# Peripheral_Circuit_A.net
KiCad netlist of a schematic drawn in Altium Designer
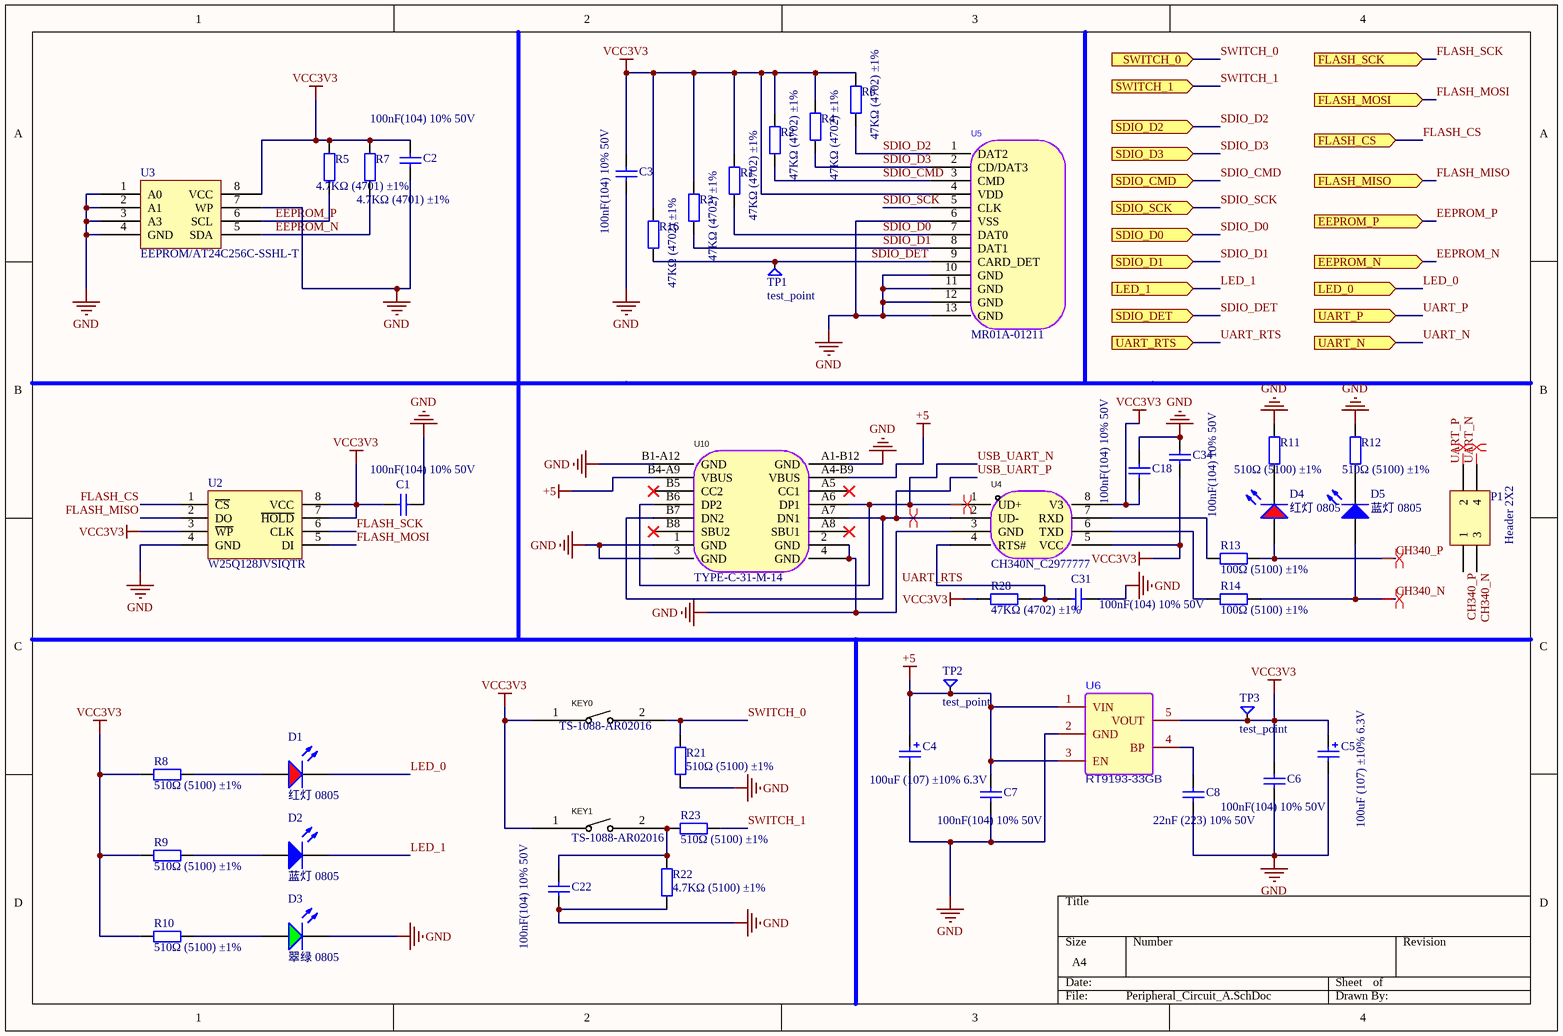
[diagram p0: Peripheral_Circuit_A.SchDoc]

(export (version "E")
  (design (tool "Eeschema 10.0.6"))
  (components
    (comp (ref "C1")
      (value "100nF(104) 10% 50V")
      (footprint "0805_C")
      (description "贴片电容")
      (libsource (lib "Miscellaneous Devices LC") (part "0805 100nF(104) 10% 50V"))
    )
    (comp (ref "C2")
      (value "100nF(104) 10% 50V")
      (footprint "0805_C")
      (description "贴片电容")
      (libsource (lib "Miscellaneous Devices LC") (part "0805 100nF(104) 10% 50V"))
    )
    (comp (ref "C3")
      (value "100nF(104) 10% 50V")
      (footprint "0805_C")
      (description "贴片电容")
      (libsource (lib "Miscellaneous Devices LC") (part "0805 100nF(104) 10% 50V"))
    )
    (comp (ref "C4")
      (value "100uF (107) ±10% 6.3V")
      (footprint "CAP-SMD_BD5.0-L5.3-W5.3-LS6.1-FD-1")
      (description "钽电容")
      (libsource (lib "Miscellaneous Devices LC") (part "3528 100uF (107) 10% 6.3V"))
    )
    (comp (ref "C5")
      (value "100uF (107) ±10% 6.3V")
      (footprint "CAP-SMD_BD5.0-L5.3-W5.3-LS6.1-FD-1")
      (description "钽电容")
      (libsource (lib "Miscellaneous Devices LC") (part "3528 100uF (107) 10% 6.3V"))
    )
    (comp (ref "C6")
      (value "100nF(104) 10% 50V")
      (footprint "0805_C")
      (description "贴片电容")
      (libsource (lib "Miscellaneous Devices LC") (part "0805 100nF(104) 10% 50V"))
    )
    (comp (ref "C7")
      (value "100nF(104) 10% 50V")
      (footprint "0805_C")
      (description "贴片电容")
      (libsource (lib "Miscellaneous Devices LC") (part "0805 100nF(104) 10% 50V"))
    )
    (comp (ref "C8")
      (value "22nF (223) 10% 50V")
      (footprint "0805_C")
      (description "贴片电容")
      (libsource (lib "Miscellaneous Devices LC") (part "0805 22nF (223) 10% 50V"))
    )
    (comp (ref "C18")
      (value "100nF(104) 10% 50V")
      (footprint "0805_C")
      (description "贴片电容")
      (libsource (lib "Miscellaneous Devices LC") (part "0805 100nF(104) 10% 50V"))
    )
    (comp (ref "C22")
      (value "100nF(104) 10% 50V")
      (footprint "0805_C")
      (description "贴片电容")
      (libsource (lib "Miscellaneous Devices LC") (part "0805 100nF(104) 10% 50V"))
    )
    (comp (ref "C31")
      (value "100nF(104) 10% 50V")
      (footprint "0805_C")
      (description "贴片电容")
      (libsource (lib "Miscellaneous Devices LC") (part "0805 100nF(104) 10% 50V"))
    )
    (comp (ref "C34")
      (value "100nF(104) 10% 50V")
      (footprint "0805_C")
      (description "贴片电容")
      (libsource (lib "Miscellaneous Devices LC") (part "0805 100nF(104) 10% 50V"))
    )
    (comp (ref "D1")
      (value "红灯 0805")
      (footprint "0805_LED_S1")
      (description "发光二极管")
      (libsource (lib "LED") (part "0805 红灯"))
    )
    (comp (ref "D2")
      (value "蓝灯 0805")
      (footprint "0805_LED_S1")
      (description "发光二极管")
      (libsource (lib "LED") (part "0805 蓝灯"))
    )
    (comp (ref "D3")
      (value "翠绿 0805")
      (footprint "0805_LED_S1")
      (description "发光二极管")
      (libsource (lib "LED") (part "0805 翠绿"))
    )
    (comp (ref "D4")
      (value "红灯 0805")
      (footprint "0805_LED_S1")
      (description "发光二极管")
      (libsource (lib "LED") (part "0805 红灯"))
    )
    (comp (ref "D5")
      (value "蓝灯 0805")
      (footprint "0805_LED_S1")
      (description "发光二极管")
      (libsource (lib "LED") (part "0805 蓝灯"))
    )
    (comp (ref "KEY0")
      (value "TS-1088-AR02016")
      (footprint "SW-SMD_L3.9-W3.0-P4.45")
      (description "轻触开关")
      (fields (field (name "MANUFACTURER") "XUNPU(讯普)"))
      (libsource (lib "EXTRA") (part "TS-1088-AR02016"))
    )
    (comp (ref "KEY1")
      (value "TS-1088-AR02016")
      (footprint "SW-SMD_L3.9-W3.0-P4.45")
      (description "轻触开关")
      (fields (field (name "MANUFACTURER") "XUNPU(讯普)"))
      (libsource (lib "EXTRA") (part "TS-1088-AR02016"))
    )
    (comp (ref "P1")
      (value "Header 2X2")
      (footprint "HDR2X2")
      (description "Header, 2-Pin, Dual row")
      (fields (field (name "PUBLISHER") "Altium Limited"))
      (libsource (lib "Miscellaneous Connectors") (part "Header 2X2"))
    )
    (comp (ref "R1")
      (value "47KΩ (4702) ±1%")
      (footprint "0805_R")
      (description "贴片电阻")
      (libsource (lib "Miscellaneous Devices LC") (part "0805 47KΩ (4702) 1%"))
    )
    (comp (ref "R2")
      (value "47KΩ (4702) ±1%")
      (footprint "0805_R")
      (description "贴片电阻")
      (libsource (lib "Miscellaneous Devices LC") (part "0805 47KΩ (4702) 1%"))
    )
    (comp (ref "R3")
      (value "47KΩ (4702) ±1%")
      (footprint "0805_R")
      (description "贴片电阻")
      (libsource (lib "Miscellaneous Devices LC") (part "0805 47KΩ (4702) 1%"))
    )
    (comp (ref "R4")
      (value "47KΩ (4702) ±1%")
      (footprint "0805_R")
      (description "贴片电阻")
      (libsource (lib "Miscellaneous Devices LC") (part "0805 47KΩ (4702) 1%"))
    )
    (comp (ref "R5")
      (value "4.7KΩ (4701) ±1%")
      (footprint "0805_R")
      (description "贴片电阻")
      (libsource (lib "Miscellaneous Devices LC") (part "0805 4.7KΩ (4701) 1%"))
    )
    (comp (ref "R6")
      (value "47KΩ (4702) ±1%")
      (footprint "0805_R")
      (description "贴片电阻")
      (libsource (lib "Miscellaneous Devices LC") (part "0805 47KΩ (4702) 1%"))
    )
    (comp (ref "R7")
      (value "4.7KΩ (4701) ±1%")
      (footprint "0805_R")
      (description "贴片电阻")
      (libsource (lib "Miscellaneous Devices LC") (part "0805 4.7KΩ (4701) 1%"))
    )
    (comp (ref "R8")
      (value "510Ω (5100) ±1%")
      (footprint "0805_R")
      (description "贴片电阻")
      (libsource (lib "Miscellaneous Devices LC") (part "0805 510Ω (5100) 1%"))
    )
    (comp (ref "R9")
      (value "510Ω (5100) ±1%")
      (footprint "0805_R")
      (description "贴片电阻")
      (libsource (lib "Miscellaneous Devices LC") (part "0805 510Ω (5100) 1%"))
    )
    (comp (ref "R10")
      (value "510Ω (5100) ±1%")
      (footprint "0805_R")
      (description "贴片电阻")
      (libsource (lib "Miscellaneous Devices LC") (part "0805 510Ω (5100) 1%"))
    )
    (comp (ref "R11")
      (value "510Ω (5100) ±1%")
      (footprint "0805_R")
      (description "贴片电阻")
      (libsource (lib "") (part "0805 510Ω (5100) 1%_1"))
    )
    (comp (ref "R12")
      (value "510Ω (5100) ±1%")
      (footprint "0805_R")
      (description "贴片电阻")
      (libsource (lib "") (part "0805 510Ω (5100) 1%_1"))
    )
    (comp (ref "R13")
      (value "100Ω (5100) ±1%")
      (footprint "0805_R")
      (description "贴片电阻")
      (libsource (lib "Miscellaneous Devices LC") (part "0805 510Ω (5100) 1%"))
    )
    (comp (ref "R14")
      (value "100Ω (5100) ±1%")
      (footprint "0805_R")
      (description "贴片电阻")
      (libsource (lib "Miscellaneous Devices LC") (part "0805 510Ω (5100) 1%"))
    )
    (comp (ref "R16")
      (value "47KΩ (4702) ±1%")
      (footprint "0805_R")
      (description "贴片电阻")
      (libsource (lib "Miscellaneous Devices LC") (part "0805 47KΩ (4702) 1%"))
    )
    (comp (ref "R21")
      (value "510Ω (5100) ±1%")
      (footprint "0805_R")
      (description "贴片电阻")
      (libsource (lib "") (part "0805 510Ω (5100) 1%_2"))
    )
    (comp (ref "R22")
      (value "4.7KΩ (5100) ±1%")
      (footprint "0805_R")
      (description "贴片电阻")
      (libsource (lib "") (part "0805 510Ω (5100) 1%_1"))
    )
    (comp (ref "R23")
      (value "510Ω (5100) ±1%")
      (footprint "0805_R")
      (description "贴片电阻")
      (libsource (lib "Miscellaneous Devices LC") (part "0805 510Ω (5100) 1%"))
    )
    (comp (ref "R28")
      (value "47KΩ (4702) ±1%")
      (footprint "0805_R")
      (description "贴片电阻")
      (libsource (lib "") (part "0805 47KΩ (4702) 1%_1"))
    )
    (comp (ref "TP1")
      (value "test_point")
      (footprint "test_point")
      (description "测量点")
      (libsource (lib "EXTRA") (part "test_point"))
    )
    (comp (ref "TP2")
      (value "test_point")
      (footprint "test_point")
      (description "测量点")
      (libsource (lib "EXTRA") (part "test_point"))
    )
    (comp (ref "TP3")
      (value "test_point")
      (footprint "test_point")
      (description "测量点")
      (libsource (lib "EXTRA") (part "test_point"))
    )
    (comp (ref "U2")
      (value "W25Q128JVSIQTR")
      (footprint "CH340_N")
      (description "Flash ROM")
      (libsource (lib "IC") (part "W25Q128JVSIQTR_[C97521]"))
    )
    (comp (ref "U3")
      (value "EEPROM/AT24C256C-SSHL-T")
      (footprint "CH340_N")
      (description "EEPROM")
      (libsource (lib "IC") (part "EEPROM/AT24C256C-SSHL-T_[C6482]"))
    )
    (comp (ref "U4")
      (value "CH340N_C2977777")
      (footprint "CH340_N")
      (description "TTL串口phy")
      (fields (field (name "DESIGNER") "U?"))
      (libsource (lib "EXTRA") (part "CH340N_C2977777"))
    )
    (comp (ref "U5")
      (value "MR01A-01211")
      (footprint "TF-SMD_MR01A-01211")
      (fields (field (name "MANUFACTURER") "ATOM(爱特姆)"))
      (libsource (lib "EXTRA") (part "MR01A-01211"))
    )
    (comp (ref "U6")
      (value "RT9193-33GB")
      (footprint "RT9193-33GB")
      (libsource (lib "EXTRA") (part "RT9193-33GB"))
    )
    (comp (ref "U10")
      (value "TYPE-C-31-M-14")
      (footprint "TYPE-C-31-M-14")
      (description "type-c接口")
      (fields (field (name "MANUFACTURER") "韩国韩荣"))
      (libsource (lib "EXTRA") (part "TYPE-C-31-M-14_1"))
    )
  )
  (nets
    (net (code "1") (name "+5") (class "Default")
      (node (ref "C4") (pin "1") (pinfunction "1_1") (pintype "passive"))
      (node (ref "C7") (pin "2") (pinfunction "2_2") (pintype "passive"))
      (node (ref "TP2") (pin "1") (pinfunction "1_1") (pintype "passive"))
      (node (ref "U10") (pin "A4-B9") (pinfunction "VBUS_A4-B9") (pintype "passive"))
      (node (ref "U10") (pin "B4-A9") (pinfunction "VBUS_B4-A9") (pintype "passive"))
      (node (ref "U6") (pin "1") (pinfunction "VIN_1") (pintype "passive"))
      (node (ref "U6") (pin "3") (pinfunction "EN_3") (pintype "passive"))
    )
    (net (code "2") (name "/CH340_N") (class "Default")
      (node (ref "D5") (pin "A") (pinfunction "A_A") (pintype "passive"))
      (node (ref "P1") (pin "3") (pinfunction "3_3") (pintype "passive"))
      (node (ref "R14") (pin "2") (pinfunction "2_2") (pintype "passive"))
    )
    (net (code "3") (name "/CH340_P") (class "Default")
      (node (ref "D4") (pin "A") (pinfunction "A_A") (pintype "passive"))
      (node (ref "P1") (pin "1") (pinfunction "1_1") (pintype "passive"))
      (node (ref "R13") (pin "2") (pinfunction "2_2") (pintype "passive"))
    )
    (net (code "4") (name "/EEPROM_N") (class "Default")
      (node (ref "R7") (pin "1") (pinfunction "1_1") (pintype "passive"))
      (node (ref "U3") (pin "5") (pinfunction "SDA_5") (pintype "passive"))
    )
    (net (code "5") (name "/EEPROM_P") (class "Default")
      (node (ref "R5") (pin "1") (pinfunction "1_1") (pintype "passive"))
      (node (ref "U3") (pin "6") (pinfunction "SCL_6") (pintype "passive"))
    )
    (net (code "6") (name "/FLASH_CS") (class "Default")
      (node (ref "U2") (pin "1") (pinfunction "~{CS}_1") (pintype "passive"))
    )
    (net (code "7") (name "/FLASH_MISO") (class "Default")
      (node (ref "U2") (pin "2") (pinfunction "DO_2") (pintype "passive"))
    )
    (net (code "8") (name "/FLASH_MOSI") (class "Default")
      (node (ref "U2") (pin "5") (pinfunction "DI_5") (pintype "passive"))
    )
    (net (code "9") (name "/FLASH_SCK") (class "Default")
      (node (ref "U2") (pin "6") (pinfunction "CLK_6") (pintype "passive"))
    )
    (net (code "10") (name "/LED_0") (class "Default")
      (node (ref "D1") (pin "K") (pinfunction "K_K") (pintype "passive"))
    )
    (net (code "11") (name "/LED_1") (class "Default")
      (node (ref "D2") (pin "K") (pinfunction "K_K") (pintype "passive"))
    )
    (net (code "12") (name "/SDIO_CMD") (class "Default")
      (node (ref "R2") (pin "1") (pinfunction "1_1") (pintype "passive"))
      (node (ref "U5") (pin "3") (pinfunction "CMD_3") (pintype "passive"))
    )
    (net (code "13") (name "/SDIO_D0") (class "Default")
      (node (ref "R1") (pin "1") (pinfunction "1_1") (pintype "passive"))
      (node (ref "U5") (pin "7") (pinfunction "DAT0_7") (pintype "passive"))
    )
    (net (code "14") (name "/SDIO_D1") (class "Default")
      (node (ref "R3") (pin "1") (pinfunction "1_1") (pintype "passive"))
      (node (ref "U5") (pin "8") (pinfunction "DAT1_8") (pintype "passive"))
    )
    (net (code "15") (name "/SDIO_D2") (class "Default")
      (node (ref "R6") (pin "1") (pinfunction "1_1") (pintype "passive"))
      (node (ref "U5") (pin "1") (pinfunction "DAT2_1") (pintype "passive"))
    )
    (net (code "16") (name "/SDIO_D3") (class "Default")
      (node (ref "R4") (pin "1") (pinfunction "1_1") (pintype "passive"))
      (node (ref "U5") (pin "2") (pinfunction "CD/DAT3_2") (pintype "passive"))
    )
    (net (code "17") (name "/SDIO_DET") (class "Default")
      (node (ref "R16") (pin "1") (pinfunction "1_1") (pintype "passive"))
      (node (ref "TP1") (pin "1") (pinfunction "1_1") (pintype "passive"))
      (node (ref "U5") (pin "9") (pinfunction "CARD_DET_9") (pintype "passive"))
    )
    (net (code "18") (name "/SDIO_SCK") (class "Default")
      (node (ref "U5") (pin "5") (pinfunction "CLK_5") (pintype "passive"))
    )
    (net (code "19") (name "/SWITCH_0") (class "Default")
      (node (ref "KEY0") (pin "2") (pinfunction "2_2") (pintype "passive"))
      (node (ref "R21") (pin "1") (pinfunction "1_1") (pintype "passive"))
    )
    (net (code "20") (name "/SWITCH_1") (class "Default")
      (node (ref "R23") (pin "2") (pinfunction "2_2") (pintype "passive"))
    )
    (net (code "21") (name "/UART_N") (class "Default")
      (node (ref "P1") (pin "4") (pinfunction "4_4") (pintype "passive"))
    )
    (net (code "22") (name "/UART_P") (class "Default")
      (node (ref "P1") (pin "2") (pinfunction "2_2") (pintype "passive"))
    )
    (net (code "23") (name "/UART_RTS") (class "Default")
      (node (ref "C31") (pin "2") (pinfunction "2_2") (pintype "passive"))
      (node (ref "R28") (pin "1") (pinfunction "1_1") (pintype "passive"))
      (node (ref "U4") (pin "4") (pinfunction "RTS#_4") (pintype "passive"))
    )
    (net (code "24") (name "/USB_UART_N") (class "Default")
      (node (ref "U10") (pin "A6") (pinfunction "DP1_A6") (pintype "passive"))
      (node (ref "U10") (pin "B6") (pinfunction "DP2_B6") (pintype "passive"))
      (node (ref "U4") (pin "1") (pinfunction "UD+_1") (pintype "passive"))
    )
    (net (code "25") (name "/USB_UART_P") (class "Default")
      (node (ref "U10") (pin "A7") (pinfunction "DN1_A7") (pintype "passive"))
      (node (ref "U10") (pin "B7") (pinfunction "DN2_B7") (pintype "passive"))
      (node (ref "U4") (pin "2") (pinfunction "UD-_2") (pintype "passive"))
    )
    (net (code "26") (name "GND") (class "Default")
      (node (ref "C1") (pin "2") (pinfunction "2_2") (pintype "passive"))
      (node (ref "C18") (pin "1") (pinfunction "1_1") (pintype "passive"))
      (node (ref "C2") (pin "1") (pinfunction "1_1") (pintype "passive"))
      (node (ref "C22") (pin "1") (pinfunction "1_1") (pintype "passive"))
      (node (ref "C3") (pin "1") (pinfunction "1_1") (pintype "passive"))
      (node (ref "C31") (pin "1") (pinfunction "1_1") (pintype "passive"))
      (node (ref "C34") (pin "1") (pinfunction "1_1") (pintype "passive"))
      (node (ref "C4") (pin "2") (pinfunction "2_2") (pintype "passive"))
      (node (ref "C5") (pin "2") (pinfunction "2_2") (pintype "passive"))
      (node (ref "C6") (pin "1") (pinfunction "1_1") (pintype "passive"))
      (node (ref "C7") (pin "1") (pinfunction "1_1") (pintype "passive"))
      (node (ref "C8") (pin "1") (pinfunction "1_1") (pintype "passive"))
      (node (ref "D3") (pin "K") (pinfunction "K_K") (pintype "passive"))
      (node (ref "R11") (pin "2") (pinfunction "2_2") (pintype "passive"))
      (node (ref "R12") (pin "2") (pinfunction "2_2") (pintype "passive"))
      (node (ref "R21") (pin "2") (pinfunction "2_2") (pintype "passive"))
      (node (ref "R22") (pin "1") (pinfunction "1_1") (pintype "passive"))
      (node (ref "U10") (pin "1") (pinfunction "GND_1") (pintype "passive"))
      (node (ref "U10") (pin "2") (pinfunction "GND_2") (pintype "passive"))
      (node (ref "U10") (pin "3") (pinfunction "GND_3") (pintype "passive"))
      (node (ref "U10") (pin "4") (pinfunction "GND_4") (pintype "passive"))
      (node (ref "U10") (pin "A1-B12") (pinfunction "GND_A1-B12") (pintype "passive"))
      (node (ref "U10") (pin "B1-A12") (pinfunction "GND_B1-A12") (pintype "passive"))
      (node (ref "U2") (pin "4") (pinfunction "GND_4") (pintype "passive"))
      (node (ref "U3") (pin "1") (pinfunction "A0_1") (pintype "passive"))
      (node (ref "U3") (pin "2") (pinfunction "A1_2") (pintype "passive"))
      (node (ref "U3") (pin "3") (pinfunction "A3_3") (pintype "passive"))
      (node (ref "U3") (pin "4") (pinfunction "GND_4") (pintype "passive"))
      (node (ref "U3") (pin "7") (pinfunction "WP_7") (pintype "passive"))
      (node (ref "U4") (pin "3") (pinfunction "GND_3") (pintype "passive"))
      (node (ref "U5") (pin "10") (pinfunction "GND_10") (pintype "passive"))
      (node (ref "U5") (pin "11") (pinfunction "GND_11") (pintype "passive"))
      (node (ref "U5") (pin "12") (pinfunction "GND_12") (pintype "passive"))
      (node (ref "U5") (pin "13") (pinfunction "GND_13") (pintype "passive"))
      (node (ref "U5") (pin "6") (pinfunction "VSS_6") (pintype "passive"))
      (node (ref "U6") (pin "2") (pinfunction "GND_2") (pintype "passive"))
    )
    (net (code "27") (name "Net-(C22-Pad2)") (class "Default")
      (node (ref "C22") (pin "2") (pinfunction "2_2") (pintype "passive"))
      (node (ref "KEY1") (pin "2") (pinfunction "2_2") (pintype "passive"))
      (node (ref "R22") (pin "2") (pinfunction "2_2") (pintype "passive"))
      (node (ref "R23") (pin "1") (pinfunction "1_1") (pintype "passive"))
    )
    (net (code "28") (name "Net-(D1-PadA)") (class "Default")
      (node (ref "D1") (pin "A") (pinfunction "A_A") (pintype "passive"))
      (node (ref "R8") (pin "2") (pinfunction "2_2") (pintype "passive"))
    )
    (net (code "29") (name "Net-(D2-PadA)") (class "Default")
      (node (ref "D2") (pin "A") (pinfunction "A_A") (pintype "passive"))
      (node (ref "R9") (pin "2") (pinfunction "2_2") (pintype "passive"))
    )
    (net (code "30") (name "Net-(D3-PadA)") (class "Default")
      (node (ref "D3") (pin "A") (pinfunction "A_A") (pintype "passive"))
      (node (ref "R10") (pin "2") (pinfunction "2_2") (pintype "passive"))
    )
    (net (code "31") (name "Net-(D4-PadK)") (class "Default")
      (node (ref "D4") (pin "K") (pinfunction "K_K") (pintype "passive"))
      (node (ref "R11") (pin "1") (pinfunction "1_1") (pintype "passive"))
    )
    (net (code "32") (name "Net-(D5-PadK)") (class "Default")
      (node (ref "D5") (pin "K") (pinfunction "K_K") (pintype "passive"))
      (node (ref "R12") (pin "1") (pinfunction "1_1") (pintype "passive"))
    )
    (net (code "33") (name "Net-(U4-RXD)") (class "Default")
      (node (ref "R13") (pin "1") (pinfunction "1_1") (pintype "passive"))
      (node (ref "U4") (pin "7") (pinfunction "RXD_7") (pintype "passive"))
    )
    (net (code "34") (name "Net-(U4-TXD)") (class "Default")
      (node (ref "R14") (pin "1") (pinfunction "1_1") (pintype "passive"))
      (node (ref "U4") (pin "6") (pinfunction "TXD_6") (pintype "passive"))
    )
    (net (code "35") (name "Net-(U6-BP)") (class "Default")
      (node (ref "C8") (pin "2") (pinfunction "2_2") (pintype "passive"))
      (node (ref "U6") (pin "4") (pinfunction "BP_4") (pintype "passive"))
    )
    (net (code "36") (name "VCC3V3") (class "Default")
      (node (ref "C1") (pin "1") (pinfunction "1_1") (pintype "passive"))
      (node (ref "C18") (pin "2") (pinfunction "2_2") (pintype "passive"))
      (node (ref "C2") (pin "2") (pinfunction "2_2") (pintype "passive"))
      (node (ref "C3") (pin "2") (pinfunction "2_2") (pintype "passive"))
      (node (ref "C34") (pin "2") (pinfunction "2_2") (pintype "passive"))
      (node (ref "C5") (pin "1") (pinfunction "1_1") (pintype "passive"))
      (node (ref "C6") (pin "2") (pinfunction "2_2") (pintype "passive"))
      (node (ref "KEY0") (pin "1") (pinfunction "1_1") (pintype "passive"))
      (node (ref "KEY1") (pin "1") (pinfunction "1_1") (pintype "passive"))
      (node (ref "R1") (pin "2") (pinfunction "2_2") (pintype "passive"))
      (node (ref "R10") (pin "1") (pinfunction "1_1") (pintype "passive"))
      (node (ref "R16") (pin "2") (pinfunction "2_2") (pintype "passive"))
      (node (ref "R2") (pin "2") (pinfunction "2_2") (pintype "passive"))
      (node (ref "R28") (pin "2") (pinfunction "2_2") (pintype "passive"))
      (node (ref "R3") (pin "2") (pinfunction "2_2") (pintype "passive"))
      (node (ref "R4") (pin "2") (pinfunction "2_2") (pintype "passive"))
      (node (ref "R5") (pin "2") (pinfunction "2_2") (pintype "passive"))
      (node (ref "R6") (pin "2") (pinfunction "2_2") (pintype "passive"))
      (node (ref "R7") (pin "2") (pinfunction "2_2") (pintype "passive"))
      (node (ref "R8") (pin "1") (pinfunction "1_1") (pintype "passive"))
      (node (ref "R9") (pin "1") (pinfunction "1_1") (pintype "passive"))
      (node (ref "TP3") (pin "1") (pinfunction "1_1") (pintype "passive"))
      (node (ref "U2") (pin "3") (pinfunction "~{WP}_3") (pintype "passive"))
      (node (ref "U2") (pin "7") (pinfunction "~{HOLD}_7") (pintype "passive"))
      (node (ref "U2") (pin "8") (pinfunction "VCC_8") (pintype "passive"))
      (node (ref "U3") (pin "8") (pinfunction "VCC_8") (pintype "passive"))
      (node (ref "U4") (pin "5") (pinfunction "VCC_5") (pintype "passive"))
      (node (ref "U4") (pin "8") (pinfunction "V3_8") (pintype "passive"))
      (node (ref "U5") (pin "4") (pinfunction "VDD_4") (pintype "passive"))
      (node (ref "U6") (pin "5") (pinfunction "VOUT_5") (pintype "passive"))
    )
    (net (code "37") (name "unconnected-(U10-CC1-PadA5)") (class "Default")
      (node (ref "U10") (pin "A5") (pinfunction "CC1_A5") (pintype "passive+no_connect"))
    )
    (net (code "38") (name "unconnected-(U10-CC2-PadB5)") (class "Default")
      (node (ref "U10") (pin "B5") (pinfunction "CC2_B5") (pintype "passive+no_connect"))
    )
    (net (code "39") (name "unconnected-(U10-SBU1-PadA8)") (class "Default")
      (node (ref "U10") (pin "A8") (pinfunction "SBU1_A8") (pintype "passive+no_connect"))
    )
    (net (code "40") (name "unconnected-(U10-SBU2-PadB8)") (class "Default")
      (node (ref "U10") (pin "B8") (pinfunction "SBU2_B8") (pintype "passive+no_connect"))
    )
  )
)
